# Motor_Outputs.net
KiCad netlist of a schematic drawn in Altium Designer
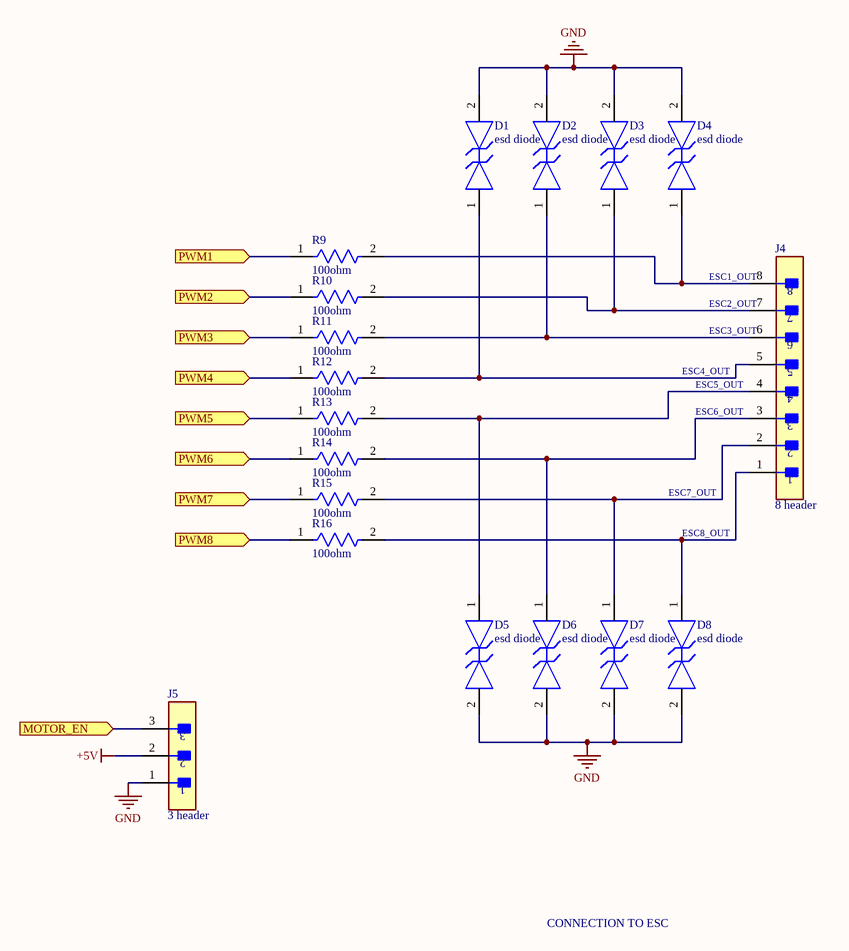
[diagram p0: Motor_Outputs.SchDoc]

(export (version "E")
  (design (tool "Eeschema 10.0.6"))
  (components
    (comp (ref "D1")
      (value "esd diode")
      (footprint "FP-152AF-MFG")
      (description "TVS DIODE 5.3V 14V 2X3DFN")
      (libsource (lib "Altium Content Vault") (part "9a4650ba5e636bd8b2e4c4fb393e9aa"))
    )
    (comp (ref "D2")
      (value "esd diode")
      (footprint "FP-152AF-MFG")
      (description "TVS DIODE 5.3V 14V 2X3DFN")
      (libsource (lib "Altium Content Vault") (part "9a4650ba5e636bd8b2e4c4fb393e9aa"))
    )
    (comp (ref "D3")
      (value "esd diode")
      (footprint "FP-152AF-MFG")
      (description "TVS DIODE 5.3V 14V 2X3DFN")
      (libsource (lib "Altium Content Vault") (part "9a4650ba5e636bd8b2e4c4fb393e9aa"))
    )
    (comp (ref "D4")
      (value "esd diode")
      (footprint "FP-152AF-MFG")
      (description "TVS DIODE 5.3V 14V 2X3DFN")
      (libsource (lib "Altium Content Vault") (part "9a4650ba5e636bd8b2e4c4fb393e9aa"))
    )
    (comp (ref "D5")
      (value "esd diode")
      (footprint "FP-152AF-MFG")
      (description "TVS DIODE 5.3V 14V 2X3DFN")
      (libsource (lib "Altium Content Vault") (part "9a4650ba5e636bd8b2e4c4fb393e9aa"))
    )
    (comp (ref "D6")
      (value "esd diode")
      (footprint "FP-152AF-MFG")
      (description "TVS DIODE 5.3V 14V 2X3DFN")
      (libsource (lib "Altium Content Vault") (part "9a4650ba5e636bd8b2e4c4fb393e9aa"))
    )
    (comp (ref "D7")
      (value "esd diode")
      (footprint "FP-152AF-MFG")
      (description "TVS DIODE 5.3V 14V 2X3DFN")
      (libsource (lib "Altium Content Vault") (part "9a4650ba5e636bd8b2e4c4fb393e9aa"))
    )
    (comp (ref "D8")
      (value "esd diode")
      (footprint "FP-152AF-MFG")
      (description "TVS DIODE 5.3V 14V 2X3DFN")
      (libsource (lib "Altium Content Vault") (part "9a4650ba5e636bd8b2e4c4fb393e9aa"))
    )
    (comp (ref "J4")
      (value "8 header")
      (footprint "FP-B8B-XH-A_LF_SN-MFG")
      (description "CONN HEADER VERT 8POS 2.5MM")
      (libsource (lib "Altium Content Vault") (part "99ec2b232beb5d2356d4d77f6a047f0"))
    )
    (comp (ref "J5")
      (value "3 header")
      (footprint "FP-B3B-XH-AM_LF_SN-MFG")
      (description "CONN HEADER VERT 3POS 2.5MM")
      (libsource (lib "Altium Content Vault") (part "0d3f023dd272f625e17a2be33dea85f"))
    )
    (comp (ref "R9")
      (value "100ohm")
      (footprint "FP-RNCP0603-MFG")
      (description "100Ω ±1% 0.125W 0603 High Power Anti-Sulfur Thin Film Chip Resistor")
      (fields (field (name "TOLERANCE") "1%"))
      (libsource (lib "Altium Content Vault") (part "1029c3af85768c4190bb7ad29bc67b5"))
    )
    (comp (ref "R10")
      (value "100ohm")
      (footprint "FP-RNCP0603-MFG")
      (description "100Ω ±1% 0.125W 0603 High Power Anti-Sulfur Thin Film Chip Resistor")
      (fields (field (name "TOLERANCE") "1%"))
      (libsource (lib "Altium Content Vault") (part "1029c3af85768c4190bb7ad29bc67b5"))
    )
    (comp (ref "R11")
      (value "100ohm")
      (footprint "FP-RNCP0603-MFG")
      (description "100Ω ±1% 0.125W 0603 High Power Anti-Sulfur Thin Film Chip Resistor")
      (fields (field (name "TOLERANCE") "1%"))
      (libsource (lib "Altium Content Vault") (part "1029c3af85768c4190bb7ad29bc67b5"))
    )
    (comp (ref "R12")
      (value "100ohm")
      (footprint "FP-RNCP0603-MFG")
      (description "100Ω ±1% 0.125W 0603 High Power Anti-Sulfur Thin Film Chip Resistor")
      (fields (field (name "TOLERANCE") "1%"))
      (libsource (lib "Altium Content Vault") (part "1029c3af85768c4190bb7ad29bc67b5"))
    )
    (comp (ref "R13")
      (value "100ohm")
      (footprint "FP-RNCP0603-MFG")
      (description "100Ω ±1% 0.125W 0603 High Power Anti-Sulfur Thin Film Chip Resistor")
      (fields (field (name "TOLERANCE") "1%"))
      (libsource (lib "Altium Content Vault") (part "1029c3af85768c4190bb7ad29bc67b5"))
    )
    (comp (ref "R14")
      (value "100ohm")
      (footprint "FP-RNCP0603-MFG")
      (description "100Ω ±1% 0.125W 0603 High Power Anti-Sulfur Thin Film Chip Resistor")
      (fields (field (name "TOLERANCE") "1%"))
      (libsource (lib "Altium Content Vault") (part "1029c3af85768c4190bb7ad29bc67b5"))
    )
    (comp (ref "R15")
      (value "100ohm")
      (footprint "FP-RNCP0603-MFG")
      (description "100Ω ±1% 0.125W 0603 High Power Anti-Sulfur Thin Film Chip Resistor")
      (fields (field (name "TOLERANCE") "1%"))
      (libsource (lib "Altium Content Vault") (part "1029c3af85768c4190bb7ad29bc67b5"))
    )
    (comp (ref "R16")
      (value "100ohm")
      (footprint "FP-RNCP0603-MFG")
      (description "100Ω ±1% 0.125W 0603 High Power Anti-Sulfur Thin Film Chip Resistor")
      (fields (field (name "TOLERANCE") "1%"))
      (libsource (lib "Altium Content Vault") (part "1029c3af85768c4190bb7ad29bc67b5"))
    )
  )
  (nets
    (net (code "1") (name "+5V") (class "Default")
      (node (ref "J5") (pin "2") (pinfunction "2_2") (pintype "passive"))
    )
    (net (code "2") (name "/MOTOR_EN") (class "Default")
      (node (ref "J5") (pin "3") (pinfunction "3_3") (pintype "passive"))
    )
    (net (code "3") (name "/PWM1") (class "Default")
      (node (ref "R9") (pin "1") (pinfunction "1_1") (pintype "passive"))
    )
    (net (code "4") (name "/PWM2") (class "Default")
      (node (ref "R10") (pin "1") (pinfunction "1_1") (pintype "passive"))
    )
    (net (code "5") (name "/PWM3") (class "Default")
      (node (ref "R11") (pin "1") (pinfunction "1_1") (pintype "passive"))
    )
    (net (code "6") (name "/PWM4") (class "Default")
      (node (ref "R12") (pin "1") (pinfunction "1_1") (pintype "passive"))
    )
    (net (code "7") (name "/PWM5") (class "Default")
      (node (ref "R13") (pin "1") (pinfunction "1_1") (pintype "passive"))
    )
    (net (code "8") (name "/PWM6") (class "Default")
      (node (ref "R14") (pin "1") (pinfunction "1_1") (pintype "passive"))
    )
    (net (code "9") (name "/PWM7") (class "Default")
      (node (ref "R15") (pin "1") (pinfunction "1_1") (pintype "passive"))
    )
    (net (code "10") (name "/PWM8") (class "Default")
      (node (ref "R16") (pin "1") (pinfunction "1_1") (pintype "passive"))
    )
    (net (code "11") (name "GND") (class "Default")
      (node (ref "D1") (pin "2") (pinfunction "2_2") (pintype "passive"))
      (node (ref "D2") (pin "2") (pinfunction "2_2") (pintype "passive"))
      (node (ref "D3") (pin "2") (pinfunction "2_2") (pintype "passive"))
      (node (ref "D4") (pin "2") (pinfunction "2_2") (pintype "passive"))
      (node (ref "D5") (pin "2") (pinfunction "2_2") (pintype "passive"))
      (node (ref "D6") (pin "2") (pinfunction "2_2") (pintype "passive"))
      (node (ref "D7") (pin "2") (pinfunction "2_2") (pintype "passive"))
      (node (ref "D8") (pin "2") (pinfunction "2_2") (pintype "passive"))
      (node (ref "J5") (pin "1") (pinfunction "1_1") (pintype "passive"))
    )
    (net (code "12") (name "Net-(D1-Pad1)") (class "Default")
      (node (ref "D1") (pin "1") (pinfunction "1_1") (pintype "passive"))
      (node (ref "J4") (pin "5") (pinfunction "5_5") (pintype "passive"))
      (node (ref "R12") (pin "2") (pinfunction "2_2") (pintype "passive"))
    )
    (net (code "13") (name "Net-(D2-Pad1)") (class "Default")
      (node (ref "D2") (pin "1") (pinfunction "1_1") (pintype "passive"))
      (node (ref "J4") (pin "6") (pinfunction "6_6") (pintype "passive"))
      (node (ref "R11") (pin "2") (pinfunction "2_2") (pintype "passive"))
    )
    (net (code "14") (name "Net-(D3-Pad1)") (class "Default")
      (node (ref "D3") (pin "1") (pinfunction "1_1") (pintype "passive"))
      (node (ref "J4") (pin "7") (pinfunction "7_7") (pintype "passive"))
      (node (ref "R10") (pin "2") (pinfunction "2_2") (pintype "passive"))
    )
    (net (code "15") (name "Net-(D4-Pad1)") (class "Default")
      (node (ref "D4") (pin "1") (pinfunction "1_1") (pintype "passive"))
      (node (ref "J4") (pin "8") (pinfunction "8_8") (pintype "passive"))
      (node (ref "R9") (pin "2") (pinfunction "2_2") (pintype "passive"))
    )
    (net (code "16") (name "Net-(D5-Pad1)") (class "Default")
      (node (ref "D5") (pin "1") (pinfunction "1_1") (pintype "passive"))
      (node (ref "J4") (pin "4") (pinfunction "4_4") (pintype "passive"))
      (node (ref "R13") (pin "2") (pinfunction "2_2") (pintype "passive"))
    )
    (net (code "17") (name "Net-(D6-Pad1)") (class "Default")
      (node (ref "D6") (pin "1") (pinfunction "1_1") (pintype "passive"))
      (node (ref "J4") (pin "3") (pinfunction "3_3") (pintype "passive"))
      (node (ref "R14") (pin "2") (pinfunction "2_2") (pintype "passive"))
    )
    (net (code "18") (name "Net-(D7-Pad1)") (class "Default")
      (node (ref "D7") (pin "1") (pinfunction "1_1") (pintype "passive"))
      (node (ref "J4") (pin "2") (pinfunction "2_2") (pintype "passive"))
      (node (ref "R15") (pin "2") (pinfunction "2_2") (pintype "passive"))
    )
    (net (code "19") (name "Net-(D8-Pad1)") (class "Default")
      (node (ref "D8") (pin "1") (pinfunction "1_1") (pintype "passive"))
      (node (ref "J4") (pin "1") (pinfunction "1_1") (pintype "passive"))
      (node (ref "R16") (pin "2") (pinfunction "2_2") (pintype "passive"))
    )
  )
)
